# PDB.net
KiCad netlist of a schematic drawn in Altium Designer
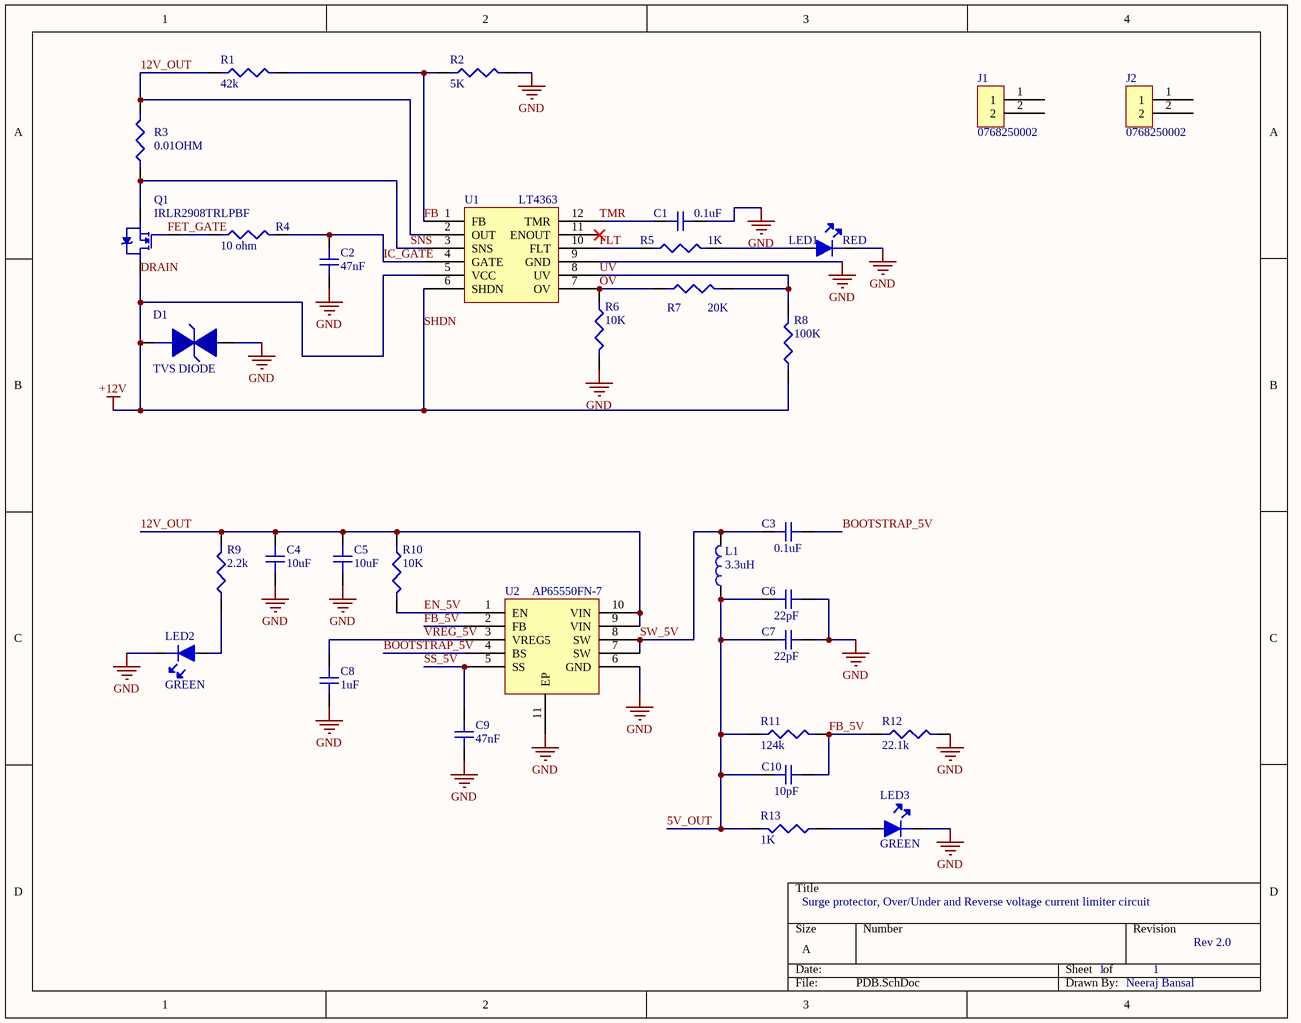
[diagram p0: PDB.SchDoc]

(export (version "E")
  (design (tool "Eeschema 10.0.6"))
  (components
    (comp (ref "C1")
      (value "0.1uF")
      (footprint "PDB_Components:CAPC1613X09N")
      (description "0.1µF ±10% 25V Ceramic Capacitor X5R 0603 (1608 Metric)")
      (fields
        (field (name "MANUFACTURER") "Murata")
        (field (name "MANUFACTURER PART NUMBER") "GCM188R71H473KA55D")
      )
      (libsource (lib "PDB") (part "CL10A104KA8NNNC"))
    )
    (comp (ref "C2")
      (value "47nF")
      (footprint "PDB_Components:CAPC1613X09N")
      (description "CAP CER 0.047UF 50V X7R 0603")
      (fields
        (field (name "MANUFACTURER") "Murata")
        (field (name "MANUFACTURER PART NUMBER") "GCM188R71H473KA55D")
      )
      (libsource (lib "PDB") (part "GCM188R71H473KA55D"))
    )
    (comp (ref "C3")
      (value "0.1uF")
      (footprint "PDB_Components:CAPC1613X09N")
      (description "0.1µF ±10% 25V Ceramic Capacitor X5R 0603 (1608 Metric)")
      (fields
        (field (name "MANUFACTURER") "Murata")
        (field (name "MANUFACTURER PART NUMBER") "GCM188R71H473KA55D")
      )
      (libsource (lib "PDB") (part "CL10A104KA8NNNC"))
    )
    (comp (ref "C4")
      (value "10uF")
      (footprint "PDB_Components:CAPC1613X09N")
      (description "10µF ±10% 10V Ceramic Capacitor X7R 0805 (2012 Metric)")
      (fields
        (field (name "MANUFACTURER") "Murata")
        (field (name "MANUFACTURER PART NUMBER") "GCM188R71H473KA55D")
      )
      (libsource (lib "PDB") (part "GRM21BR71A106KA73L"))
    )
    (comp (ref "C5")
      (value "10uF")
      (footprint "PDB_Components:CAPC1613X09N")
      (description "10µF ±10% 10V Ceramic Capacitor X7R 0805 (2012 Metric)")
      (fields
        (field (name "MANUFACTURER") "Murata")
        (field (name "MANUFACTURER PART NUMBER") "GCM188R71H473KA55D")
      )
      (libsource (lib "PDB") (part "GRM21BR71A106KA73L"))
    )
    (comp (ref "C6")
      (value "22pF")
      (footprint "PDB_Components:CAPC1613X09N")
      (description "22µF ±10% 10V Ceramic Capacitor X7R 1206 (3216 Metric)")
      (fields
        (field (name "MANUFACTURER") "Murata")
        (field (name "MANUFACTURER PART NUMBER") "GCM188R71H473KA55D")
      )
      (libsource (lib "PDB") (part "CL31B226KPHNNNE"))
    )
    (comp (ref "C7")
      (value "22pF")
      (footprint "PDB_Components:CAPC1613X09N")
      (description "22µF ±10% 10V Ceramic Capacitor X7R 1206 (3216 Metric)")
      (fields
        (field (name "MANUFACTURER") "Murata")
        (field (name "MANUFACTURER PART NUMBER") "GCM188R71H473KA55D")
      )
      (libsource (lib "PDB") (part "CL31B226KPHNNNE"))
    )
    (comp (ref "C8")
      (value "1uF")
      (footprint "PDB_Components:CAPC1613X09N")
      (description "1µF ±10% 50V Ceramic Capacitor X7R 0805 (2012 Metric)")
      (fields
        (field (name "MANUFACTURER") "Murata")
        (field (name "MANUFACTURER PART NUMBER") "GCM188R71H473KA55D")
      )
      (libsource (lib "PDB") (part "CL21B105KBFVPNE"))
    )
    (comp (ref "C9")
      (value "47nF")
      (footprint "PDB_Components:CAPC1613X09N")
      (description "CAP CER 0.047UF 50V X7R 0603")
      (fields
        (field (name "MANUFACTURER") "Murata")
        (field (name "MANUFACTURER PART NUMBER") "GCM188R71H473KA55D")
      )
      (libsource (lib "PDB") (part "GCM188R71H473KA55D"))
    )
    (comp (ref "C10")
      (value "10pF")
      (footprint "PDB_Components:CAPC1613X09N")
      (description "10pF ±10% 50V Ceramic Capacitor X7R 0805 (2012 Metric)")
      (fields
        (field (name "MANUFACTURER") "Murata")
        (field (name "MANUFACTURER PART NUMBER") "GCM188R71H473KA55D")
      )
      (libsource (lib "PDB") (part "C0805C100K5RAC7800"))
    )
    (comp (ref "D1")
      (value "TVS DIODE")
      (footprint "PDB_Components:DIODE_TVS")
      (description "TVS DIODE 58VWM 93.6VC SMA")
      (fields (field (name "MANUFACTURER") "Diodes") (field (name "MANUFACTURER PART NUMBER") "SMAJ58A-13-F"))
      (libsource (lib "PDB") (part "SMAJ58A-13-F"))
    )
    (comp (ref "J1")
      (value "0768250002")
      (footprint "PDB_Components:MOLEX_2PIN_MEGAFIT")
      (description "CONN_2Position_MEGAFIT Molex Through Hole, Right Angle Tin")
      (fields (field (name "MANUFACTURER") "Molex"))
      (libsource (lib "PDB") (part "0768250002"))
    )
    (comp (ref "J2")
      (value "0768250002")
      (footprint "PDB_Components:MOLEX_2PIN_MEGAFIT")
      (description "CONN_2Position_MEGAFIT Molex Through Hole, Right Angle Tin")
      (fields (field (name "MANUFACTURER") "Molex"))
      (libsource (lib "PDB") (part "0768250002"))
    )
    (comp (ref "L1")
      (value "3.3uH")
      (footprint "PDB_Components:IND-6mm")
      (description "IND 3.3µH 6.5A 25.2 mOhm Max Nonstandard")
      (fields
        (field (name "MANUFACTURER") "Murata")
        (field (name "MANUFACTURER PART NUMBER") "1264EY-3R3N=P3")
      )
      (libsource (lib "PDB") (part "1264EY-3R3N=P3"))
    )
    (comp (ref "LED1")
      (value "RED")
      (footprint "PDB_Components:LED2")
      (description "Red  LED Indication - Discrete 2V 0603 (1608 Metric)")
      (fields
        (field (name "MANUFACTURER") "Wurth Electronics")
        (field (name "MANUFACTURER PART NUMBER") "150060VS75000")
      )
      (libsource (lib "PDB") (part "QTLP600CRTR"))
    )
    (comp (ref "LED2")
      (value "GREEN")
      (footprint "PDB_Components:LED2")
      (description "LED GREEN CLEAR 0603 SMD")
      (fields
        (field (name "MANUFACTURER") "Wurth Electronics")
        (field (name "MANUFACTURER PART NUMBER") "150060VS75000")
      )
      (libsource (lib "PDB") (part "150060VS75000"))
    )
    (comp (ref "LED3")
      (value "GREEN")
      (footprint "PDB_Components:LED2")
      (description "LED GREEN CLEAR 0603 SMD")
      (fields
        (field (name "MANUFACTURER") "Wurth Electronics")
        (field (name "MANUFACTURER PART NUMBER") "150060VS75000")
      )
      (libsource (lib "PDB") (part "150060VS75000"))
    )
    (comp (ref "Q1")
      (value "IRLR2908TRLPBF")
      (footprint "PDB_Components:DPAK")
      (description "MOSFET N-CH 80V 30A DPAK")
      (fields (field (name "MANUFACTURER") "International Rectifier"))
      (libsource (lib "PDB") (part "IRLR2908TRLPBF"))
    )
    (comp (ref "R1")
      (value "42k")
      (footprint "PDB_Components:R0805")
      (fields
        (field (name "MANUFACTURER") "Stackpole Electronics")
        (field (name "MANUFACTURER PART NUMBER") "RNCF0805DTE10K0")
        (field (name "TOLERANCE") "0.5%")
      )
      (libsource (lib "PDB") (part "RNCF0805DTE10K0_2_2"))
    )
    (comp (ref "R2")
      (value "5K")
      (footprint "PDB_Components:R0805")
      (fields
        (field (name "MANUFACTURER") "Vishay Dale Thin Film")
        (field (name "MANUFACTURER PART NUMBER") "PNM0805E5001BST5")
        (field (name "TOLERANCE") "0.1%")
      )
      (libsource (lib "PDB") (part "PNM0805E5001BST5"))
    )
    (comp (ref "R3")
      (value "0.01OHM")
      (footprint "PDB_Components:R2512")
      (description "RES SMD 0.01 OHM 1% 2W 2512")
      (fields
        (field (name "MANUFACTURER") "Yageo")
        (field (name "MANUFACTURER PART NUMBER") "PE2512FKE7W0R01L")
      )
      (libsource (lib "PDB") (part "PE2512FKE7W0R01L"))
    )
    (comp (ref "R4")
      (value "10 ohm")
      (footprint "PDB_Components:R0805")
      (description "RES SMD 10 OHM 1% 1/3W 0805")
      (fields
        (field (name "MANUFACTURER") "Susumu")
        (field (name "MANUFACTURER PART NUMBER") "RL1220S-100-F")
      )
      (libsource (lib "PDB") (part "RL1220S-100-F"))
    )
    (comp (ref "R5")
      (value "1K")
      (footprint "PDB_Components:R0805")
      (description "1 kOhms ±0.5% 0.125W, 1/8W Chip Resistor 0805 (2012 Metric) Automotive AEC-Q200 Thin Film")
      (fields
        (field (name "MANUFACTURER") "Stackpole Electronics")
        (field (name "MANUFACTURER PART NUMBER") "RNCF0805DTE10K0")
      )
      (libsource (lib "PDB") (part "RNCF0805DTE1K00"))
    )
    (comp (ref "R6")
      (value "10K")
      (footprint "PDB_Components:R0805")
      (description "Res Thin Film 0805 10K Ohm 0.5% 0.1W(1/10W) ±25ppm/C Molded SMD Paper T/R")
      (fields
        (field (name "MANUFACTURER") "Stackpole Electronics")
        (field (name "MANUFACTURER PART NUMBER") "RNCF0805DTE10K0")
      )
      (libsource (lib "PDB") (part "RNCF0805DTE10K0"))
    )
    (comp (ref "R7")
      (value "20K")
      (footprint "PDB_Components:R0805")
      (description "20 kOhms ±0.5% 0.125W, 1/8W Chip Resistor 0805 (2012 Metric) Automotive AEC-Q200 Thin Film")
      (fields
        (field (name "MANUFACTURER") "Stackpole Electronics")
        (field (name "MANUFACTURER PART NUMBER") "RNCF0805DTE10K0")
      )
      (libsource (lib "PDB") (part "RNCF0805DTE20K0"))
    )
    (comp (ref "R8")
      (value "100K")
      (footprint "PDB_Components:R0805")
      (description "Res Thin Film 0805 100K Ohm 0.1% 0.125W(1/8W) ±25ppm/C Molded SMD Automotive Punched T/R")
      (fields
        (field (name "MANUFACTURER") "Panasonic")
        (field (name "MANUFACTURER PART NUMBER") "ERA-6AEB104V")
      )
      (libsource (lib "PDB") (part "ERA-6AEB104V"))
    )
    (comp (ref "R9")
      (value "2.2k")
      (footprint "PDB_Components:R0805")
      (description "2.2 kOhms ±1% 0.125W, 1/8W Chip Resistor 0805 (2012 Metric) Moisture Resistant Thick Film")
      (fields
        (field (name "MANUFACTURER") "Stackpole Electronics")
        (field (name "MANUFACTURER PART NUMBER") "RNCF0805DTE10K0")
      )
      (libsource (lib "PDB") (part "RC0805FR-072K2L"))
    )
    (comp (ref "R10")
      (value "10K")
      (footprint "PDB_Components:R0805")
      (description "Res Thin Film 0805 10K Ohm 0.5% 0.1W(1/10W) ±25ppm/C Molded SMD Paper T/R")
      (fields
        (field (name "MANUFACTURER") "Stackpole Electronics")
        (field (name "MANUFACTURER PART NUMBER") "RNCF0805DTE10K0")
      )
      (libsource (lib "PDB") (part "RNCF0805DTE10K0"))
    )
    (comp (ref "R11")
      (value "124k")
      (footprint "PDB_Components:R0805")
      (description "124 kOhms ±0.1% 0.125W, 1/8W Chip Resistor 0805 (2012 Metric) Automotive AEC-Q200 Thin Film")
      (fields
        (field (name "MANUFACTURER") "Stackpole Electronics")
        (field (name "MANUFACTURER PART NUMBER") "RNCF0805DTE10K0")
      )
      (libsource (lib "PDB") (part "ERA-6AEB1243V"))
    )
    (comp (ref "R12")
      (value "22.1k")
      (footprint "PDB_Components:R0805")
      (description "22.1 kOhms ±0.5% 0.125W, 1/8W Chip Resistor 0805 (2012 Metric) Automotive AEC-Q200 Thin Film")
      (fields
        (field (name "MANUFACTURER") "Stackpole Electronics")
        (field (name "MANUFACTURER PART NUMBER") "RNCF0805DTE10K0")
      )
      (libsource (lib "PDB") (part "RNCF0805DTE22K1"))
    )
    (comp (ref "R13")
      (value "1K")
      (footprint "PDB_Components:R0805")
      (description "1 kOhms ±0.5% 0.125W, 1/8W Chip Resistor 0805 (2012 Metric) Automotive AEC-Q200 Thin Film")
      (fields
        (field (name "MANUFACTURER") "Stackpole Electronics")
        (field (name "MANUFACTURER PART NUMBER") "RNCF0805DTE10K0")
      )
      (libsource (lib "PDB") (part "RNCF0805DTE1K00"))
    )
    (comp (ref "U1")
      (value "LT4363")
      (footprint "PDB_Components:TSOP65P490X110-12N")
      (description "IC SURGE STOPPER HV 12-MSOP")
      (fields
        (field (name "MANUFACTURER") "Analog Devices / Linear Technology")
        (field (name "MANUFACTURER PART NUMBER") "LT4363CMS-2#PBF")
      )
      (libsource (lib "PDB") (part "LT4363CMS-2#PBF"))
    )
    (comp (ref "U2")
      (value "AP65550FN-7")
      (footprint "PDB_Components:DFN-10")
      (description "IC BUCK SYNC 5A, 18V VIN MAX 650kHz COT Step-Down Conv")
      (fields (field (name "MANUFACTURER") "Diodes"))
      (libsource (lib "PDB") (part "AP65550FN-7"))
    )
  )
  (nets
    (net (code "1") (name "+12V") (class "Default")
      (node (ref "D1") (pin "2") (pinfunction "2_2") (pintype "passive"))
      (node (ref "Q1") (pin "4") (pinfunction "4_4") (pintype "passive"))
      (node (ref "R8") (pin "1") (pinfunction "1_1") (pintype "passive"))
      (node (ref "U1") (pin "5") (pinfunction "VCC_5") (pintype "passive"))
      (node (ref "U1") (pin "6") (pinfunction "SHDN_6") (pintype "passive"))
    )
    (net (code "2") (name "/5V_OUT") (class "Default")
      (node (ref "C10") (pin "1") (pinfunction "1_1") (pintype "passive"))
      (node (ref "C6") (pin "1") (pinfunction "1_1") (pintype "passive"))
      (node (ref "C7") (pin "1") (pinfunction "1_1") (pintype "passive"))
      (node (ref "L1") (pin "1") (pinfunction "1_1") (pintype "passive"))
      (node (ref "R11") (pin "1") (pinfunction "1_1") (pintype "passive"))
      (node (ref "R13") (pin "2") (pinfunction "2_2") (pintype "passive"))
    )
    (net (code "3") (name "/12V_OUT") (class "Default")
      (node (ref "C4") (pin "2") (pinfunction "2_2") (pintype "passive"))
      (node (ref "C5") (pin "2") (pinfunction "2_2") (pintype "passive"))
      (node (ref "R1") (pin "1") (pinfunction "1_1") (pintype "passive"))
      (node (ref "R10") (pin "1") (pinfunction "1_1") (pintype "passive"))
      (node (ref "R3") (pin "2") (pinfunction "2_2") (pintype "passive"))
      (node (ref "R9") (pin "2") (pinfunction "2_2") (pintype "passive"))
      (node (ref "U1") (pin "2") (pinfunction "OUT_2") (pintype "passive"))
      (node (ref "U2") (pin "10") (pinfunction "VIN_10") (pintype "passive"))
      (node (ref "U2") (pin "9") (pinfunction "VIN_9") (pintype "passive"))
    )
    (net (code "4") (name "/BOOTSTRAP_5V") (class "Default")
      (node (ref "C3") (pin "2") (pinfunction "2_2") (pintype "passive"))
      (node (ref "U2") (pin "4") (pinfunction "BS_4") (pintype "passive"))
    )
    (net (code "5") (name "/EN_5V") (class "Default")
      (node (ref "R10") (pin "2") (pinfunction "2_2") (pintype "passive"))
      (node (ref "U2") (pin "1") (pinfunction "EN_1") (pintype "passive"))
    )
    (net (code "6") (name "/FB") (class "Default")
      (node (ref "R1") (pin "2") (pinfunction "2_2") (pintype "passive"))
      (node (ref "R2") (pin "1") (pinfunction "1_1") (pintype "passive"))
      (node (ref "U1") (pin "1") (pinfunction "FB_1") (pintype "passive"))
    )
    (net (code "7") (name "/FB_5V") (class "Default")
      (node (ref "C10") (pin "2") (pinfunction "2_2") (pintype "passive"))
      (node (ref "R11") (pin "2") (pinfunction "2_2") (pintype "passive"))
      (node (ref "R12") (pin "1") (pinfunction "1_1") (pintype "passive"))
      (node (ref "U2") (pin "2") (pinfunction "FB_2") (pintype "passive"))
    )
    (net (code "9") (name "/FLT") (class "Default")
      (node (ref "R5") (pin "1") (pinfunction "1_1") (pintype "passive"))
      (node (ref "U1") (pin "10") (pinfunction "FLT_10") (pintype "passive"))
    )
    (net (code "10") (name "/IC_GATE") (class "Default")
      (node (ref "C2") (pin "2") (pinfunction "2_2") (pintype "passive"))
      (node (ref "R4") (pin "2") (pinfunction "2_2") (pintype "passive"))
      (node (ref "U1") (pin "4") (pinfunction "GATE_4") (pintype "passive"))
    )
    (net (code "11") (name "/OV") (class "Default")
      (node (ref "R6") (pin "1") (pinfunction "1_1") (pintype "passive"))
      (node (ref "R7") (pin "1") (pinfunction "1_1") (pintype "passive"))
      (node (ref "U1") (pin "7") (pinfunction "OV_7") (pintype "passive"))
    )
    (net (code "12") (name "/SNS") (class "Default")
      (node (ref "Q1") (pin "3") (pinfunction "3_3") (pintype "passive"))
      (node (ref "R3") (pin "1") (pinfunction "1_1") (pintype "passive"))
      (node (ref "U1") (pin "3") (pinfunction "SNS_3") (pintype "passive"))
    )
    (net (code "13") (name "/SS_5V") (class "Default")
      (node (ref "C9") (pin "2") (pinfunction "2_2") (pintype "passive"))
      (node (ref "U2") (pin "5") (pinfunction "SS_5") (pintype "passive"))
    )
    (net (code "14") (name "/SW_5V") (class "Default")
      (node (ref "C3") (pin "1") (pinfunction "1_1") (pintype "passive"))
      (node (ref "L1") (pin "2") (pinfunction "2_2") (pintype "passive"))
      (node (ref "U2") (pin "7") (pinfunction "SW_7") (pintype "passive"))
      (node (ref "U2") (pin "8") (pinfunction "SW_8") (pintype "passive"))
    )
    (net (code "15") (name "/TMR") (class "Default")
      (node (ref "C1") (pin "1") (pinfunction "1_1") (pintype "passive"))
      (node (ref "U1") (pin "12") (pinfunction "TMR_12") (pintype "passive"))
    )
    (net (code "16") (name "/UV") (class "Default")
      (node (ref "R7") (pin "2") (pinfunction "2_2") (pintype "passive"))
      (node (ref "R8") (pin "2") (pinfunction "2_2") (pintype "passive"))
      (node (ref "U1") (pin "8") (pinfunction "UV_8") (pintype "passive"))
    )
    (net (code "17") (name "/VREG_5V") (class "Default")
      (node (ref "C8") (pin "2") (pinfunction "2_2") (pintype "passive"))
      (node (ref "U2") (pin "3") (pinfunction "VREG5_3") (pintype "passive"))
    )
    (net (code "18") (name "GND") (class "Default")
      (node (ref "C1") (pin "2") (pinfunction "2_2") (pintype "passive"))
      (node (ref "C2") (pin "1") (pinfunction "1_1") (pintype "passive"))
      (node (ref "C4") (pin "1") (pinfunction "1_1") (pintype "passive"))
      (node (ref "C5") (pin "1") (pinfunction "1_1") (pintype "passive"))
      (node (ref "C6") (pin "2") (pinfunction "2_2") (pintype "passive"))
      (node (ref "C7") (pin "2") (pinfunction "2_2") (pintype "passive"))
      (node (ref "C8") (pin "1") (pinfunction "1_1") (pintype "passive"))
      (node (ref "C9") (pin "1") (pinfunction "1_1") (pintype "passive"))
      (node (ref "D1") (pin "1") (pinfunction "1_1") (pintype "passive"))
      (node (ref "LED1") (pin "2") (pinfunction "2_2") (pintype "passive"))
      (node (ref "LED2") (pin "2") (pinfunction "2_2") (pintype "passive"))
      (node (ref "LED3") (pin "2") (pinfunction "2_2") (pintype "passive"))
      (node (ref "R12") (pin "2") (pinfunction "2_2") (pintype "passive"))
      (node (ref "R2") (pin "2") (pinfunction "2_2") (pintype "passive"))
      (node (ref "R6") (pin "2") (pinfunction "2_2") (pintype "passive"))
      (node (ref "U1") (pin "9") (pinfunction "GND_9") (pintype "passive"))
      (node (ref "U2") (pin "11") (pinfunction "EP_11") (pintype "passive"))
      (node (ref "U2") (pin "6") (pinfunction "GND_6") (pintype "passive"))
    )
    (net (code "19") (name "Net-(LED1-Pad1)") (class "Default")
      (node (ref "LED1") (pin "1") (pinfunction "1_1") (pintype "passive"))
      (node (ref "R5") (pin "2") (pinfunction "2_2") (pintype "passive"))
    )
    (net (code "20") (name "Net-(LED2-Pad1)") (class "Default")
      (node (ref "LED2") (pin "1") (pinfunction "1_1") (pintype "passive"))
      (node (ref "R9") (pin "1") (pinfunction "1_1") (pintype "passive"))
    )
    (net (code "21") (name "Net-(LED3-Pad1)") (class "Default")
      (node (ref "LED3") (pin "1") (pinfunction "1_1") (pintype "passive"))
      (node (ref "R13") (pin "1") (pinfunction "1_1") (pintype "passive"))
    )
    (net (code "22") (name "Net-(Q1-Pad1)") (class "Default")
      (node (ref "Q1") (pin "1") (pinfunction "1_1") (pintype "passive"))
      (node (ref "R4") (pin "1") (pinfunction "1_1") (pintype "passive"))
    )
    (net (code "23") (name "unconnected-(J1-Pad1)") (class "Default")
      (node (ref "J1") (pin "1") (pinfunction "1_1") (pintype "passive"))
    )
    (net (code "24") (name "unconnected-(J1-Pad2)") (class "Default")
      (node (ref "J1") (pin "2") (pinfunction "2_2") (pintype "passive"))
    )
    (net (code "25") (name "unconnected-(J2-Pad1)") (class "Default")
      (node (ref "J2") (pin "1") (pinfunction "1_1") (pintype "passive"))
    )
    (net (code "26") (name "unconnected-(J2-Pad2)") (class "Default")
      (node (ref "J2") (pin "2") (pinfunction "2_2") (pintype "passive"))
    )
    (net (code "27") (name "unconnected-(U1-ENOUT-Pad11)") (class "Default")
      (node (ref "U1") (pin "11") (pinfunction "ENOUT_11") (pintype "passive+no_connect"))
    )
  )
)
